# SCH_Elektrisch_Schema_B_2022-10-21_1.net
KiCad netlist of a schematic drawn in EasyEDA
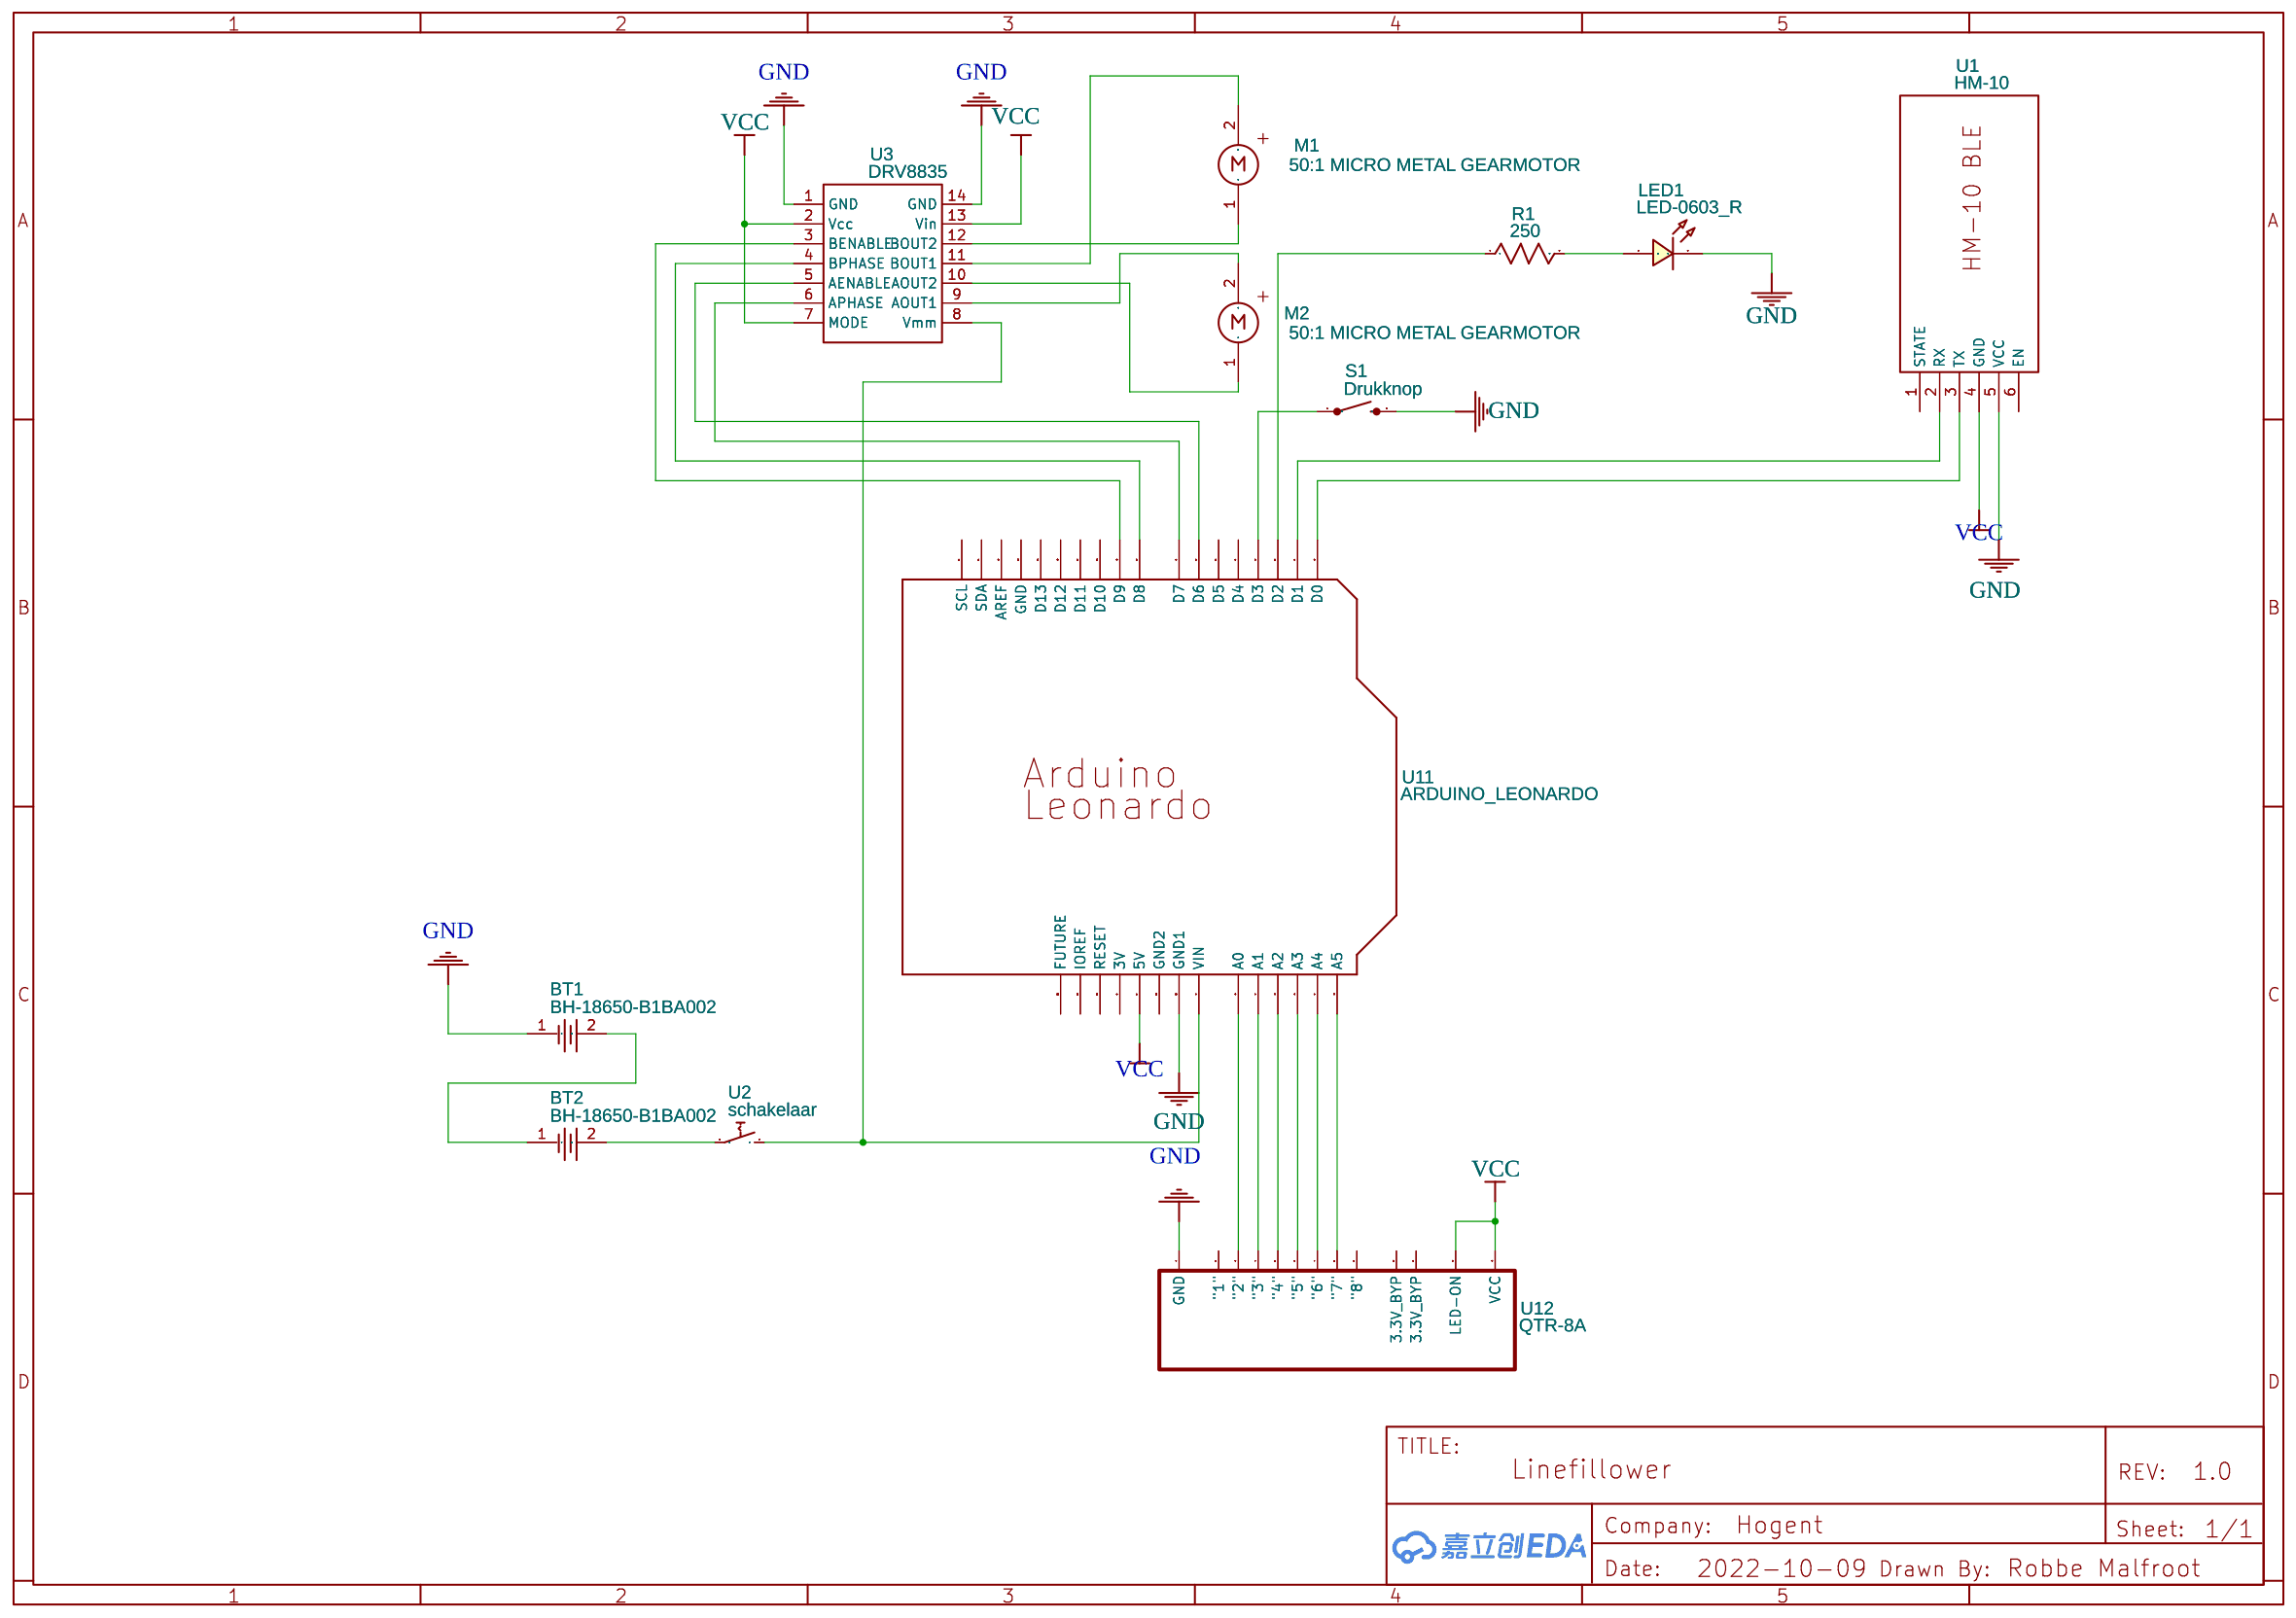
[diagram p0: schematic sheet]

(export (version "E")
  (design (tool "Eeschema 10.0.6"))
  (components
    (comp (ref "BT1")
      (value "BH-18650-B1BA002")
      (fields (field (name "BOM_Supplier Part") "C2988620"))
      (libsource (lib "") (part "BH-18650-B1BA002"))
    )
    (comp (ref "BT2")
      (value "BH-18650-B1BA002")
      (fields (field (name "BOM_Supplier Part") "C2988620"))
      (libsource (lib "") (part "BH-18650-B1BA002"))
    )
    (comp (ref "LED1")
      (value "LED-0603_R")
      (fields
        (field (name "BOM_Manufacturer Part") "19-217/R6C-AL1M2VY/3T")
        (field (name "BOM_Supplier Part") "C72044")
      )
      (libsource (lib "") (part "LED-0603_R"))
    )
    (comp (ref "M1")
      (value "50:1 MICRO METAL GEARMOTOR")
      (fields
        (field (name "BOM_Manufacturer Part") "10:1 Micro Metal Gearmotor HPCB 6V with Extended Motor Shaft")
        (field (name "BOM_Supplier Part") "3071")
      )
      (libsource (lib "") (part "10{colon}1 MICRO METAL GEARMOTOR eskere"))
    )
    (comp (ref "M2")
      (value "50:1 MICRO METAL GEARMOTOR")
      (fields
        (field (name "BOM_Manufacturer Part") "10:1 Micro Metal Gearmotor HPCB 6V with Extended Motor Shaft")
        (field (name "BOM_Supplier Part") "3071")
      )
      (libsource (lib "") (part "10{colon}1 MICRO METAL GEARMOTOR eskere"))
    )
    (comp (ref "R1") (value "250") (libsource (lib "") (part "R_0603_US")))
    (comp (ref "S1") (value "Drukknop") (libsource (lib "") (part "Drukknop")))
    (comp (ref "U1") (value "HM-10") (libsource (lib "") (part "HM-10")))
    (comp (ref "U2") (value "schakelaar") (libsource (lib "") (part "schakelaar")))
    (comp (ref "U3") (value "DRV8835") (libsource (lib "") (part "DRV8835")))
    (comp (ref "U11") (value "ARDUINO_LEONARDO") (libsource (lib "") (part "ARDUINO_LEONARDO")))
    (comp (ref "U12")
      (value "QTR-8A")
      (fields (field (name "BOM_Supplier Part") "960"))
      (libsource (lib "") (part "QTR-8A"))
    )
  )
  (nets
    (net (code "1") (name "GND") (class "Default")
      (node (ref "BT1") (pin "1") (pinfunction "1_1") (pintype "input"))
      (node (ref "LED1") (pin "2") (pinfunction "2_2") (pintype "unspecified"))
      (node (ref "S1") (pin "2") (pinfunction "2_2") (pintype "unspecified"))
      (node (ref "U1") (pin "5") (pinfunction "VCC_5") (pintype "unspecified"))
      (node (ref "U11") (pin "GND$3") (pinfunction "GND1_GND$3") (pintype "passive"))
      (node (ref "U12") (pin "1") (pinfunction "GND_1") (pintype "unspecified"))
      (node (ref "U3") (pin "1") (pinfunction "GND_1") (pintype "unspecified"))
      (node (ref "U3") (pin "14") (pinfunction "GND_14") (pintype "unspecified"))
    )
    (net (code "2") (name "Net-(BT1-Pad2)") (class "Default")
      (node (ref "BT1") (pin "2") (pinfunction "2_2") (pintype "input"))
      (node (ref "BT2") (pin "1") (pinfunction "1_1") (pintype "input"))
    )
    (net (code "3") (name "Net-(BT2-Pad2)") (class "Default")
      (node (ref "BT2") (pin "2") (pinfunction "2_2") (pintype "input"))
      (node (ref "U2") (pin "2") (pinfunction "2_2") (pintype "unspecified"))
    )
    (net (code "4") (name "Net-(LED1-Pad1)") (class "Default")
      (node (ref "LED1") (pin "1") (pinfunction "1_1") (pintype "unspecified"))
      (node (ref "R1") (pin "2") (pinfunction "2_2") (pintype "unspecified"))
    )
    (net (code "5") (name "Net-(R1-Pad1)") (class "Default")
      (node (ref "R1") (pin "1") (pinfunction "1_1") (pintype "unspecified"))
      (node (ref "U11") (pin "D2") (pinfunction "D2_D2") (pintype "unspecified"))
    )
    (net (code "6") (name "Net-(S1-Pad1)") (class "Default")
      (node (ref "S1") (pin "1") (pinfunction "1_1") (pintype "unspecified"))
      (node (ref "U11") (pin "D3") (pinfunction "D3_D3") (pintype "unspecified"))
    )
    (net (code "7") (name "Net-(U1-RX)") (class "Default")
      (node (ref "U1") (pin "2") (pinfunction "RX_2") (pintype "unspecified"))
      (node (ref "U11") (pin "D1") (pinfunction "D1_D1") (pintype "unspecified"))
    )
    (net (code "8") (name "Net-(U1-TX)") (class "Default")
      (node (ref "U1") (pin "3") (pinfunction "TX_3") (pintype "unspecified"))
      (node (ref "U11") (pin "D0") (pinfunction "D0_D0") (pintype "unspecified"))
    )
    (net (code "9") (name "Net-(U3-AENABLE)") (class "Default")
      (node (ref "U11") (pin "D6") (pinfunction "D6_D6") (pintype "unspecified"))
      (node (ref "U3") (pin "5") (pinfunction "AENABLE_5") (pintype "unspecified"))
    )
    (net (code "10") (name "Net-(U3-AOUT1)") (class "Default")
      (node (ref "M2") (pin "2") (pinfunction "2_2") (pintype "unspecified"))
      (node (ref "U3") (pin "9") (pinfunction "AOUT1_9") (pintype "unspecified"))
    )
    (net (code "11") (name "Net-(U3-AOUT2)") (class "Default")
      (node (ref "M2") (pin "1") (pinfunction "1_1") (pintype "unspecified"))
      (node (ref "U3") (pin "10") (pinfunction "AOUT2_10") (pintype "unspecified"))
    )
    (net (code "12") (name "Net-(U3-APHASE)") (class "Default")
      (node (ref "U11") (pin "D7") (pinfunction "D7_D7") (pintype "unspecified"))
      (node (ref "U3") (pin "6") (pinfunction "APHASE_6") (pintype "unspecified"))
    )
    (net (code "13") (name "Net-(U3-BENABLE)") (class "Default")
      (node (ref "U11") (pin "D9") (pinfunction "D9_D9") (pintype "unspecified"))
      (node (ref "U3") (pin "3") (pinfunction "BENABLE_3") (pintype "unspecified"))
    )
    (net (code "14") (name "Net-(U3-BOUT1)") (class "Default")
      (node (ref "M1") (pin "2") (pinfunction "2_2") (pintype "unspecified"))
      (node (ref "U3") (pin "11") (pinfunction "BOUT1_11") (pintype "unspecified"))
    )
    (net (code "15") (name "Net-(U3-BOUT2)") (class "Default")
      (node (ref "M1") (pin "1") (pinfunction "1_1") (pintype "unspecified"))
      (node (ref "U3") (pin "12") (pinfunction "BOUT2_12") (pintype "unspecified"))
    )
    (net (code "16") (name "Net-(U3-BPHASE)") (class "Default")
      (node (ref "U11") (pin "D8") (pinfunction "D8_D8") (pintype "unspecified"))
      (node (ref "U3") (pin "4") (pinfunction "BPHASE_4") (pintype "unspecified"))
    )
    (net (code "17") (name "Net-(U3-Vmm)") (class "Default")
      (node (ref "U11") (pin "VIN") (pinfunction "VIN_VIN") (pintype "passive"))
      (node (ref "U2") (pin "1") (pinfunction "1_1") (pintype "unspecified"))
      (node (ref "U3") (pin "8") (pinfunction "Vmm_8") (pintype "unspecified"))
    )
    (net (code "18") (name "Net-(U12-\"2\")") (class "Default")
      (node (ref "U11") (pin "A0") (pinfunction "A0_A0") (pintype "unspecified"))
      (node (ref "U12") (pin "3") (pinfunction "\"2\"_3") (pintype "unspecified"))
    )
    (net (code "19") (name "Net-(U12-\"3\")") (class "Default")
      (node (ref "U11") (pin "A1") (pinfunction "A1_A1") (pintype "unspecified"))
      (node (ref "U12") (pin "4") (pinfunction "\"3\"_4") (pintype "unspecified"))
    )
    (net (code "20") (name "Net-(U12-\"4\")") (class "Default")
      (node (ref "U11") (pin "A2") (pinfunction "A2_A2") (pintype "unspecified"))
      (node (ref "U12") (pin "5") (pinfunction "\"4\"_5") (pintype "unspecified"))
    )
    (net (code "21") (name "Net-(U12-\"5\")") (class "Default")
      (node (ref "U11") (pin "A3") (pinfunction "A3_A3") (pintype "unspecified"))
      (node (ref "U12") (pin "6") (pinfunction "\"5\"_6") (pintype "unspecified"))
    )
    (net (code "22") (name "Net-(U12-\"6\")") (class "Default")
      (node (ref "U11") (pin "A4") (pinfunction "A4_A4") (pintype "unspecified"))
      (node (ref "U12") (pin "7") (pinfunction "\"6\"_7") (pintype "unspecified"))
    )
    (net (code "23") (name "Net-(U12-\"7\")") (class "Default")
      (node (ref "U11") (pin "A5") (pinfunction "A5_A5") (pintype "unspecified"))
      (node (ref "U12") (pin "8") (pinfunction "\"7\"_8") (pintype "unspecified"))
    )
    (net (code "24") (name "VCC") (class "Default")
      (node (ref "U1") (pin "4") (pinfunction "GND_4") (pintype "unspecified"))
      (node (ref "U11") (pin "5V") (pinfunction "5V_5V") (pintype "passive"))
      (node (ref "U12") (pin "12") (pinfunction "LED-ON_12") (pintype "unspecified"))
      (node (ref "U3") (pin "13") (pinfunction "Vin_13") (pintype "unspecified"))
      (node (ref "U3") (pin "2") (pinfunction "Vcc_2") (pintype "unspecified"))
      (node (ref "U3") (pin "7") (pinfunction "MODE_7") (pintype "unspecified"))
    )
    (net (code "25") (name "unconnected-(U1-EN-Pad6)") (class "Default")
      (node (ref "U1") (pin "6") (pinfunction "EN_6") (pintype "unspecified"))
    )
    (net (code "26") (name "unconnected-(U1-STATE-Pad1)") (class "Default")
      (node (ref "U1") (pin "1") (pinfunction "STATE_1") (pintype "unspecified"))
    )
    (net (code "27") (name "unconnected-(U11-FUTURE-PadRESERVED)") (class "Default")
      (node (ref "U11") (pin "RESERVED") (pinfunction "FUTURE_RESERVED") (pintype "unspecified"))
    )
    (net (code "28") (name "unconnected-(U11-GND2-PadGND$2)") (class "Default")
      (node (ref "U11") (pin "GND$2") (pinfunction "GND2_GND$2") (pintype "passive"))
    )
    (net (code "29") (name "unconnected-(U11-Pad3V)") (class "Default")
      (node (ref "U11") (pin "3V") (pinfunction "3V_3V") (pintype "passive"))
    )
    (net (code "30") (name "unconnected-(U11-PadAREF)") (class "Default")
      (node (ref "U11") (pin "AREF") (pinfunction "AREF_AREF") (pintype "unspecified"))
    )
    (net (code "31") (name "unconnected-(U11-PadD4)") (class "Default")
      (node (ref "U11") (pin "D4") (pinfunction "D4_D4") (pintype "unspecified"))
    )
    (net (code "32") (name "unconnected-(U11-PadD5)") (class "Default")
      (node (ref "U11") (pin "D5") (pinfunction "D5_D5") (pintype "unspecified"))
    )
    (net (code "33") (name "unconnected-(U11-PadD10)") (class "Default")
      (node (ref "U11") (pin "D10") (pinfunction "D10_D10") (pintype "unspecified"))
    )
    (net (code "34") (name "unconnected-(U11-PadD11)") (class "Default")
      (node (ref "U11") (pin "D11") (pinfunction "D11_D11") (pintype "unspecified"))
    )
    (net (code "35") (name "unconnected-(U11-PadD12)") (class "Default")
      (node (ref "U11") (pin "D12") (pinfunction "D12_D12") (pintype "unspecified"))
    )
    (net (code "36") (name "unconnected-(U11-PadD13)") (class "Default")
      (node (ref "U11") (pin "D13") (pinfunction "D13_D13") (pintype "unspecified"))
    )
    (net (code "37") (name "unconnected-(U11-PadGND)") (class "Default")
      (node (ref "U11") (pin "GND") (pinfunction "GND_GND") (pintype "passive"))
    )
    (net (code "38") (name "unconnected-(U11-PadIOREF)") (class "Default")
      (node (ref "U11") (pin "IOREF") (pinfunction "IOREF_IOREF") (pintype "unspecified"))
    )
    (net (code "39") (name "unconnected-(U11-PadRESET)") (class "Default")
      (node (ref "U11") (pin "RESET") (pinfunction "RESET_RESET") (pintype "unspecified"))
    )
    (net (code "40") (name "unconnected-(U11-PadSCL)") (class "Default")
      (node (ref "U11") (pin "SCL") (pinfunction "SCL_SCL") (pintype "unspecified"))
    )
    (net (code "41") (name "unconnected-(U11-PadSDA)") (class "Default")
      (node (ref "U11") (pin "SDA") (pinfunction "SDA_SDA") (pintype "unspecified"))
    )
    (net (code "42") (name "unconnected-(U12-\"1\"-Pad2)") (class "Default")
      (node (ref "U12") (pin "2") (pinfunction "\"1\"_2") (pintype "unspecified"))
    )
    (net (code "43") (name "unconnected-(U12-\"8\"-Pad9)") (class "Default")
      (node (ref "U12") (pin "9") (pinfunction "\"8\"_9") (pintype "unspecified"))
    )
    (net (code "44") (name "unconnected-(U12-3.3V_BYP-Pad10)") (class "Default")
      (node (ref "U12") (pin "10") (pinfunction "3.3V_BYP_10") (pintype "unspecified"))
    )
    (net (code "45") (name "unconnected-(U12-3.3V_BYP-Pad11)") (class "Default")
      (node (ref "U12") (pin "11") (pinfunction "3.3V_BYP_11") (pintype "unspecified"))
    )
  )
)
